# sd_shield_v_1-0-0-0a.net
KiCad netlist of a schematic drawn in EAGLE
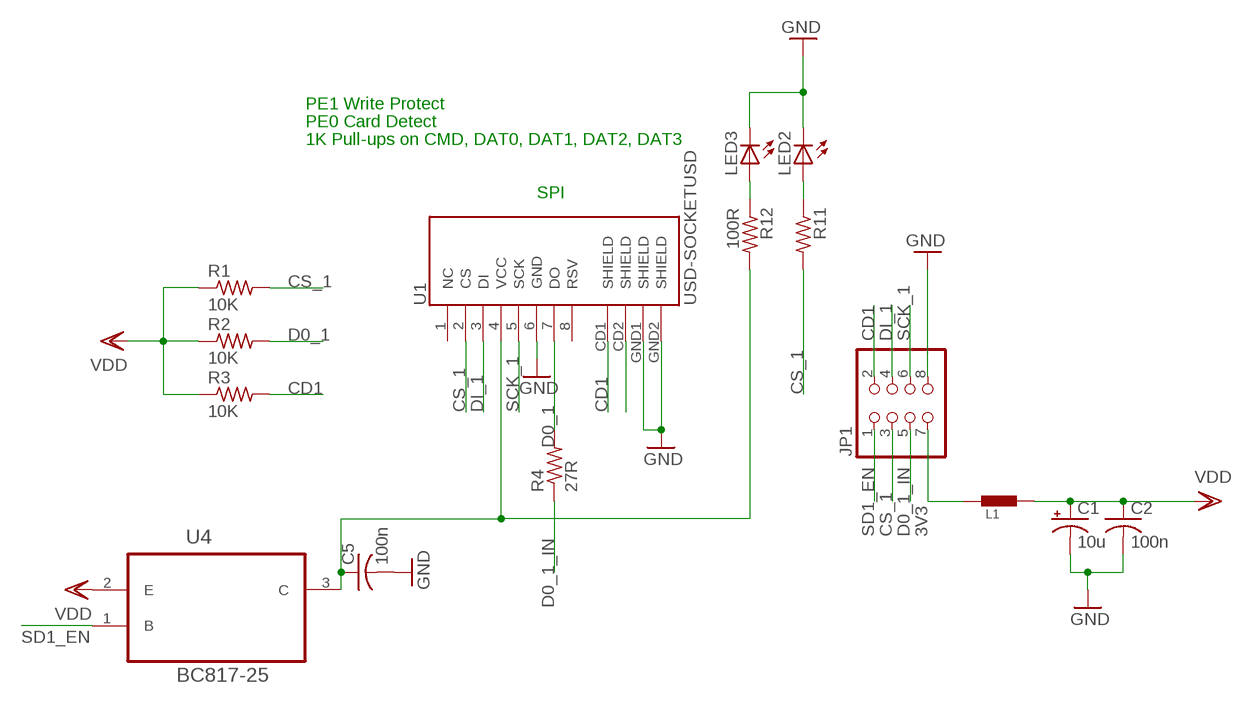
[diagram p0: schematic, sheet 1]

(export (version "E")
  (design (tool "Eeschema 10.0.6"))
  (components
    (comp (ref "C1")
      (value "10u")
      (footprint "eagle-import:B_3528-21W")
      (libsource (lib "eagle-import") (part "CPOL-USB/3528-21W"))
    )
    (comp (ref "C2")
      (value "100n")
      (footprint "eagle-import:C0603")
      (libsource (lib "eagle-import") (part "C-USC0603"))
    )
    (comp (ref "C5")
      (value "100n")
      (footprint "eagle-import:C0603")
      (libsource (lib "eagle-import") (part "C-USC0603"))
    )
    (comp (ref "JP1")
      (value "PINHD-2X4")
      (footprint "eagle-import:2X04")
      (libsource (lib "eagle-import") (part "PINHD-2X4"))
    )
    (comp (ref "L1")
      (value "FERRITE")
      (footprint "eagle-import:0805")
      (libsource (lib "eagle-import") (part "FERRITE"))
    )
    (comp (ref "LED2")
      (value "LEDCHIP-LED0603")
      (footprint "eagle-import:CHIP-LED0603")
      (libsource (lib "eagle-import") (part "LEDCHIP-LED0603"))
    )
    (comp (ref "LED3")
      (value "LEDCHIP-LED0603")
      (footprint "eagle-import:CHIP-LED0603")
      (libsource (lib "eagle-import") (part "LEDCHIP-LED0603"))
    )
    (comp (ref "R1")
      (value "10K")
      (footprint "eagle-import:R0603")
      (libsource (lib "eagle-import") (part "R-US_R0603"))
    )
    (comp (ref "R2")
      (value "10K")
      (footprint "eagle-import:R0603")
      (libsource (lib "eagle-import") (part "R-US_R0603"))
    )
    (comp (ref "R3")
      (value "10K")
      (footprint "eagle-import:R0603")
      (libsource (lib "eagle-import") (part "R-US_R0603"))
    )
    (comp (ref "R4")
      (value "27R")
      (footprint "eagle-import:R0603")
      (libsource (lib "eagle-import") (part "R-US_R0603"))
    )
    (comp (ref "R11")
      (value "R-US_R0603")
      (footprint "eagle-import:R0603")
      (libsource (lib "eagle-import") (part "R-US_R0603"))
    )
    (comp (ref "R12")
      (value "100R")
      (footprint "eagle-import:R0603")
      (libsource (lib "eagle-import") (part "R-US_R0603"))
    )
    (comp (ref "U1")
      (value "USD-SOCKETUSD")
      (footprint "eagle-import:USD-SOCKET-PP")
      (libsource (lib "eagle-import") (part "USD-SOCKETUSD"))
    )
    (comp (ref "U4")
      (value "BC817-25")
      (footprint "eagle-import:SOT95P240X97-3N")
      (libsource (lib "eagle-import") (part "BC817-25"))
    )
  )
  (nets
    (net (code "1") (name "/3V3") (class "Default")
      (node (ref "JP1") (pin "7") (pinfunction "7_7") (pintype "passive"))
      (node (ref "L1") (pin "1") (pinfunction "P$1_1") (pintype "bidirectional"))
    )
    (net (code "2") (name "/CD1") (class "Default")
      (node (ref "JP1") (pin "2") (pinfunction "2_2") (pintype "passive"))
      (node (ref "R3") (pin "2") (pinfunction "2_2") (pintype "passive"))
      (node (ref "U1") (pin "CD1") (pinfunction "SHIELD_CD1") (pintype "bidirectional"))
    )
    (net (code "3") (name "/CS_1") (class "Default")
      (node (ref "JP1") (pin "3") (pinfunction "3_3") (pintype "passive"))
      (node (ref "R1") (pin "2") (pinfunction "2_2") (pintype "passive"))
      (node (ref "R11") (pin "2") (pinfunction "2_2") (pintype "passive"))
      (node (ref "U1") (pin "2") (pinfunction "CS_2") (pintype "bidirectional"))
    )
    (net (code "4") (name "/D0_1") (class "Default")
      (node (ref "R2") (pin "2") (pinfunction "2_2") (pintype "passive"))
      (node (ref "R4") (pin "2") (pinfunction "2_2") (pintype "passive"))
      (node (ref "U1") (pin "7") (pinfunction "DO_7") (pintype "bidirectional"))
    )
    (net (code "5") (name "/D0_1_IN") (class "Default")
      (node (ref "JP1") (pin "5") (pinfunction "5_5") (pintype "passive"))
      (node (ref "R4") (pin "1") (pinfunction "1_1") (pintype "passive"))
    )
    (net (code "6") (name "/DI_1") (class "Default")
      (node (ref "JP1") (pin "4") (pinfunction "4_4") (pintype "passive"))
      (node (ref "U1") (pin "3") (pinfunction "DI_3") (pintype "bidirectional"))
    )
    (net (code "7") (name "/SCK_1") (class "Default")
      (node (ref "JP1") (pin "6") (pinfunction "6_6") (pintype "passive"))
      (node (ref "U1") (pin "5") (pinfunction "SCK_5") (pintype "bidirectional"))
    )
    (net (code "8") (name "/SD1_EN") (class "Default")
      (node (ref "JP1") (pin "1") (pinfunction "1_1") (pintype "passive"))
      (node (ref "U4") (pin "1") (pinfunction "B_1") (pintype "passive"))
    )
    (net (code "9") (name "GND") (class "Default")
      (node (ref "C1") (pin "-") (pinfunction "-_-") (pintype "passive"))
      (node (ref "C2") (pin "2") (pinfunction "2_2") (pintype "passive"))
      (node (ref "C5") (pin "2") (pinfunction "2_2") (pintype "passive"))
      (node (ref "JP1") (pin "8") (pinfunction "8_8") (pintype "passive"))
      (node (ref "LED2") (pin "C") (pinfunction "C_C") (pintype "passive"))
      (node (ref "LED3") (pin "C") (pinfunction "C_C") (pintype "passive"))
      (node (ref "U1") (pin "6") (pinfunction "GND_6") (pintype "bidirectional"))
      (node (ref "U1") (pin "GND1") (pinfunction "SHIELD_GND1") (pintype "bidirectional"))
      (node (ref "U1") (pin "GND2") (pinfunction "SHIELD_GND2") (pintype "bidirectional"))
    )
    (net (code "10") (name "Net-(LED2-PadA)") (class "Default")
      (node (ref "LED2") (pin "A") (pinfunction "A_A") (pintype "passive"))
      (node (ref "R11") (pin "1") (pinfunction "1_1") (pintype "passive"))
    )
    (net (code "11") (name "Net-(LED3-PadA)") (class "Default")
      (node (ref "LED3") (pin "A") (pinfunction "A_A") (pintype "passive"))
      (node (ref "R12") (pin "1") (pinfunction "1_1") (pintype "passive"))
    )
    (net (code "12") (name "Net-(U1-VCC)") (class "Default")
      (node (ref "C5") (pin "1") (pinfunction "1_1") (pintype "passive"))
      (node (ref "R12") (pin "2") (pinfunction "2_2") (pintype "passive"))
      (node (ref "U1") (pin "4") (pinfunction "VCC_4") (pintype "bidirectional"))
      (node (ref "U4") (pin "3") (pinfunction "C_3") (pintype "passive"))
    )
    (net (code "13") (name "VDD") (class "Default")
      (node (ref "C1") (pin "+") (pinfunction "+_+") (pintype "passive"))
      (node (ref "C2") (pin "1") (pinfunction "1_1") (pintype "passive"))
      (node (ref "L1") (pin "2") (pinfunction "P$2_2") (pintype "bidirectional"))
      (node (ref "R1") (pin "1") (pinfunction "1_1") (pintype "passive"))
      (node (ref "R2") (pin "1") (pinfunction "1_1") (pintype "passive"))
      (node (ref "R3") (pin "1") (pinfunction "1_1") (pintype "passive"))
      (node (ref "U4") (pin "2") (pinfunction "E_2") (pintype "passive"))
    )
    (net (code "14") (name "unconnected-(U1-NC-Pad1)") (class "Default")
      (node (ref "U1") (pin "1") (pinfunction "NC_1") (pintype "bidirectional"))
    )
    (net (code "15") (name "unconnected-(U1-RSV-Pad8)") (class "Default")
      (node (ref "U1") (pin "8") (pinfunction "RSV_8") (pintype "bidirectional"))
    )
    (net (code "16") (name "unconnected-(U1-SHIELD-PadCD2)") (class "Default")
      (node (ref "U1") (pin "CD2") (pinfunction "SHIELD_CD2") (pintype "bidirectional"))
    )
  )
)
